# main_rtc.net
KiCad netlist of a schematic drawn in Altium Designer
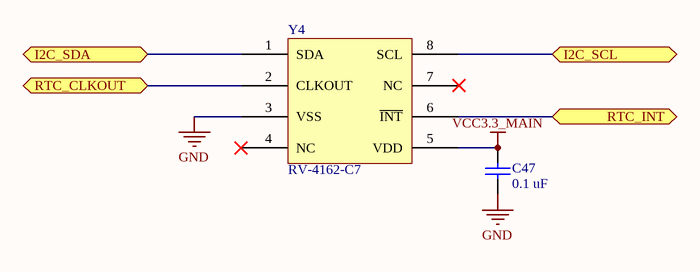
[diagram p0: main_rtc.SchDoc]

(export (version "E")
  (design (tool "Eeschema 10.0.6"))
  (components
    (comp (ref "C47")
      (value "0.1 uF")
      (footprint "0402")
      (description "Ceramic capacitor, 0.1u, 0402 package")
      (fields (field (name "TOLERANCE") "10%") (field (name "Comment") "Ceramic capacitor"))
      (libsource (lib "rlc") (part "C_0.1u_0402_ceramic"))
    )
    (comp (ref "Y4")
      (value "RV-4162-C7")
      (footprint "RV4162")
      (description "Real Time Clock Module with I2C Bus")
      (libsource (lib "crystal_oscillators_rtc") (part "RV-4162-C7"))
    )
  )
  (nets
    (net (code "1") (name "/I2C_SCL") (class "Default")
      (node (ref "Y4") (pin "8") (pinfunction "SCL_8") (pintype "passive"))
    )
    (net (code "2") (name "/I2C_SDA") (class "Default")
      (node (ref "Y4") (pin "1") (pinfunction "SDA_1") (pintype "passive"))
    )
    (net (code "3") (name "/RTC_CLKOUT") (class "Default")
      (node (ref "Y4") (pin "2") (pinfunction "CLKOUT_2") (pintype "passive"))
    )
    (net (code "4") (name "/RTC_INT") (class "Default")
      (node (ref "Y4") (pin "6") (pinfunction "~{INT}_6") (pintype "passive"))
    )
    (net (code "5") (name "GND") (class "Default")
      (node (ref "C47") (pin "2") (pintype "passive"))
      (node (ref "Y4") (pin "3") (pinfunction "VSS_3") (pintype "passive"))
    )
    (net (code "6") (name "VCC3.3_MAIN") (class "Default")
      (node (ref "C47") (pin "1") (pintype "passive"))
      (node (ref "Y4") (pin "5") (pinfunction "VDD_5") (pintype "passive"))
    )
    (net (code "7") (name "unconnected-(Y4-NC-Pad4)") (class "Default")
      (node (ref "Y4") (pin "4") (pinfunction "NC_4") (pintype "passive+no_connect"))
    )
    (net (code "8") (name "unconnected-(Y4-NC-Pad7)") (class "Default")
      (node (ref "Y4") (pin "7") (pinfunction "NC_7") (pintype "passive+no_connect"))
    )
  )
)
